# TopLevel.net
KiCad netlist of a schematic drawn in Altium Designer
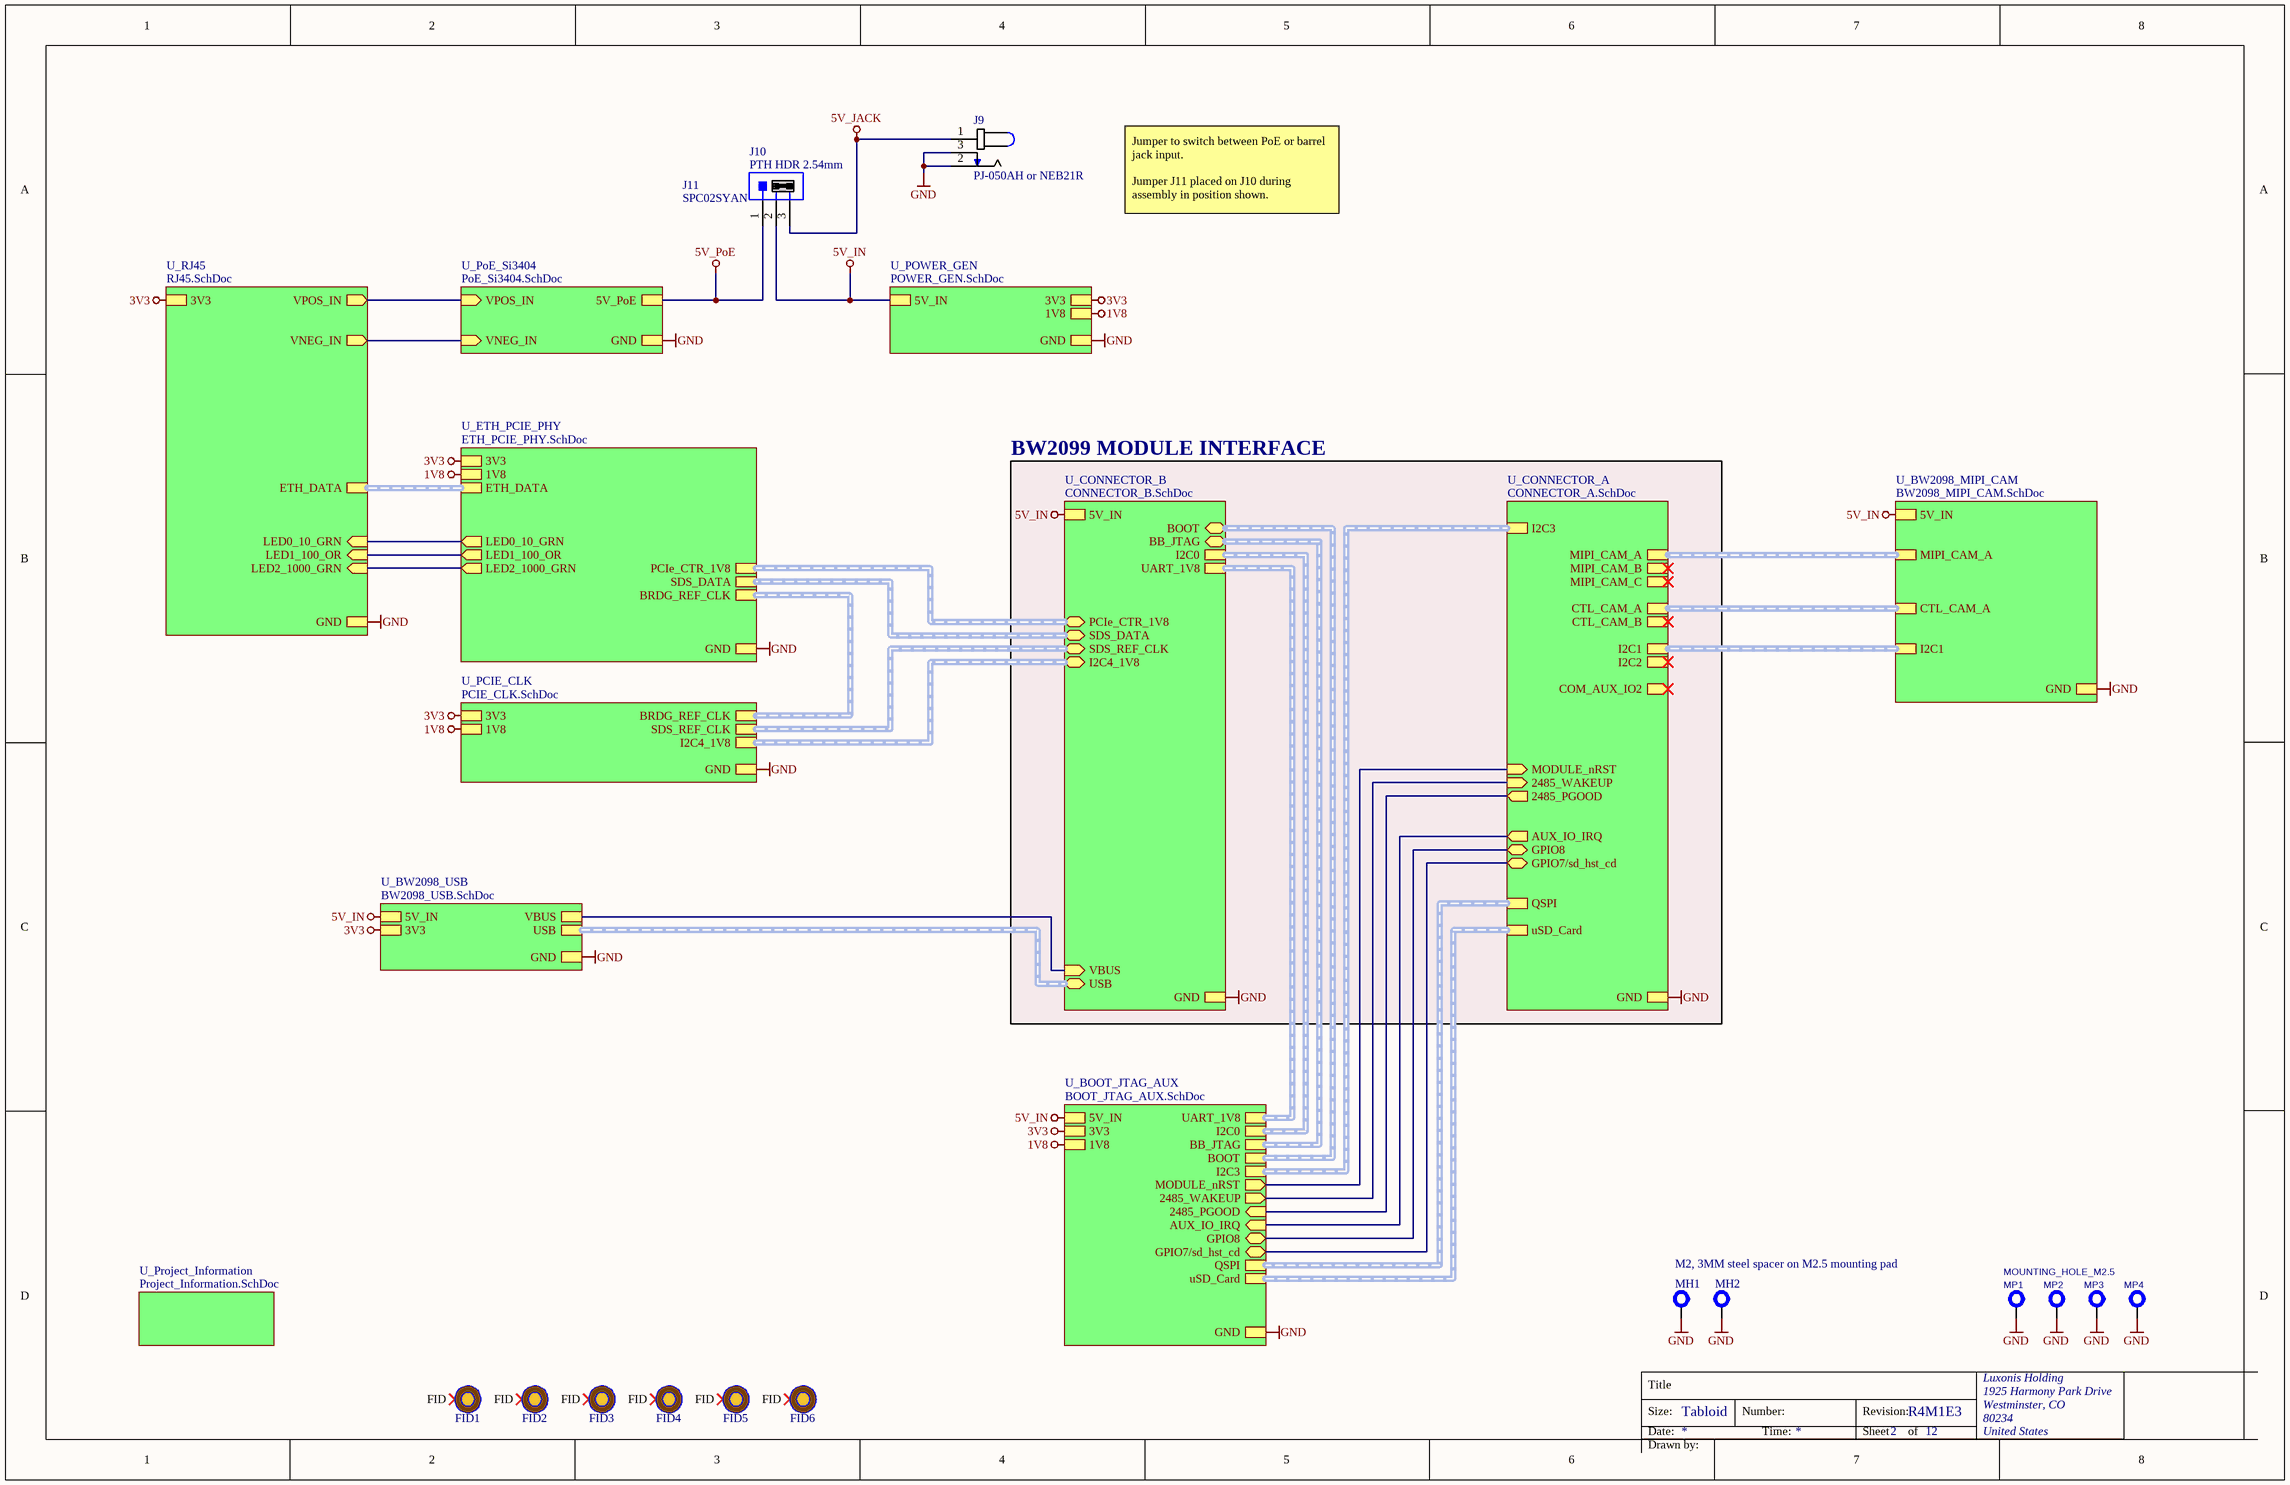
[diagram p0: TopLevel.SchDoc]

(export (version "E")
  (design (tool "Eeschema 10.0.6"))
  (components
    (comp (ref "FID1")
      (value "FIDUCIAL_ROUND_1MM")
      (footprint "LuxonisMaster:FIDUCIAL_ROUND_1MM")
      (description "Fiducial with various available footprints")
      (libsource (lib "LuxonisMaster") (part "FIDUCIAL"))
    )
    (comp (ref "FID2")
      (value "FIDUCIAL_ROUND_1MM")
      (footprint "LuxonisMaster:FIDUCIAL_ROUND_1MM")
      (description "Fiducial with various available footprints")
      (libsource (lib "LuxonisMaster") (part "FIDUCIAL"))
    )
    (comp (ref "FID3")
      (value "FIDUCIAL_ROUND_1MM")
      (footprint "LuxonisMaster:FIDUCIAL_ROUND_1MM")
      (description "Fiducial with various available footprints")
      (libsource (lib "LuxonisMaster") (part "FIDUCIAL"))
    )
    (comp (ref "FID4")
      (value "FIDUCIAL_ROUND_1MM")
      (footprint "LuxonisMaster:FIDUCIAL_ROUND_1MM")
      (description "Fiducial with various available footprints")
      (libsource (lib "LuxonisMaster") (part "FIDUCIAL"))
    )
    (comp (ref "FID5")
      (value "FIDUCIAL_ROUND_1MM")
      (footprint "LuxonisMaster:FIDUCIAL_ROUND_1MM")
      (description "Fiducial with various available footprints")
      (libsource (lib "LuxonisMaster") (part "FIDUCIAL"))
    )
    (comp (ref "FID6")
      (value "FIDUCIAL_ROUND_1MM")
      (footprint "LuxonisMaster:FIDUCIAL_ROUND_1MM")
      (description "Fiducial with various available footprints")
      (libsource (lib "LuxonisMaster") (part "FIDUCIAL"))
    )
    (comp (ref "J9")
      (value "PJ-050AH or NEB21R")
      (footprint "LuxonisMaster:PJ-050AH/NEB21R_COMBO")
      (description "CONN POWER PIN 2 POS RA PTH Barrel jack 2.1mm x 5.5mm combo footprint")
      (libsource (lib "LuxonisMaster") (part "PJ-050AH/NEB21R_COMBO"))
    )
    (comp (ref "J10")
      (value "PTH HDR 2.54mm")
      (footprint "BW2098POE:68000-103HLF")
      (description "Conn Unshrouded Header HDR 3 POS 2.54mm Solder ST Thru-Hole Bulk")
      (libsource (lib "BW2098POE") (part "68000-103HLF"))
    )
    (comp (ref "J11")
      (value "SPC02SYAN")
      (footprint "BW2098POE:SPC02SYAN")
      (description "CONN JUMPER SHORTING GOLD FLASH")
      (libsource (lib "BW2098POE") (part "SPC02SYAN"))
    )
    (comp (ref "MH1")
      (value "M2, 3MM steel spacer on M2.5 mounting pad")
      (footprint "LuxonisMaster:9774030243R")
      (description "MP ROUND STANDOFF M2X0.4 STEEL 3MM")
      (libsource (lib "LuxonisMaster") (part "9774030243R"))
    )
    (comp (ref "MH2")
      (value "M2, 3MM steel spacer on M2.5 mounting pad")
      (footprint "LuxonisMaster:9774030243R")
      (description "MP ROUND STANDOFF M2X0.4 STEEL 3MM")
      (libsource (lib "LuxonisMaster") (part "9774030243R"))
    )
    (comp (ref "MP1")
      (value "MOUNTING_HOLE_M2.5")
      (footprint "LuxonisMaster:MOUNTING_HOLE_M2.5")
      (description "=CurrentFootprint")
      (libsource (lib "LuxonisMaster") (part "MP_Mounting-Holes"))
    )
    (comp (ref "MP2")
      (value "MOUNTING_HOLE_M2.5")
      (footprint "LuxonisMaster:MOUNTING_HOLE_M2.5")
      (description "=CurrentFootprint")
      (libsource (lib "LuxonisMaster") (part "MP_Mounting-Holes"))
    )
    (comp (ref "MP3")
      (value "MOUNTING_HOLE_M2.5")
      (footprint "LuxonisMaster:MOUNTING_HOLE_M2.5")
      (description "=CurrentFootprint")
      (libsource (lib "LuxonisMaster") (part "MP_Mounting-Holes"))
    )
    (comp (ref "MP4")
      (value "MOUNTING_HOLE_M2.5")
      (footprint "LuxonisMaster:MOUNTING_HOLE_M2.5")
      (description "=CurrentFootprint")
      (libsource (lib "LuxonisMaster") (part "MP_Mounting-Holes"))
    )
  )
  (nets
    (net (code "37") (name "5V_IN") (class "Default")
      (node (ref "J10") (pin "2") (pinfunction "2_2") (pintype "passive"))
    )
    (net (code "38") (name "5V_JACK") (class "Default")
      (node (ref "J10") (pin "3") (pinfunction "3_3") (pintype "passive"))
      (node (ref "J9") (pin "1") (pinfunction "1_1") (pintype "passive"))
    )
    (net (code "39") (name "5V_PoE") (class "Default")
      (node (ref "J10") (pin "1") (pinfunction "1_1") (pintype "passive"))
    )
    (net (code "40") (name "GND") (class "Default")
      (node (ref "J9") (pin "2") (pinfunction "2_2") (pintype "passive"))
      (node (ref "J9") (pin "3") (pinfunction "3_3") (pintype "passive"))
      (node (ref "MH1") (pin "1") (pintype "passive"))
      (node (ref "MH2") (pin "1") (pintype "passive"))
      (node (ref "MP1") (pin "1") (pintype "passive"))
      (node (ref "MP2") (pin "1") (pintype "passive"))
      (node (ref "MP3") (pin "1") (pintype "passive"))
      (node (ref "MP4") (pin "1") (pintype "passive"))
    )
    (net (code "41") (name "unconnected-(FID1-PadFID)") (class "Default")
      (node (ref "FID1") (pin "FID") (pinfunction "FID_FID") (pintype "input+no_connect"))
    )
    (net (code "42") (name "unconnected-(FID2-PadFID)") (class "Default")
      (node (ref "FID2") (pin "FID") (pinfunction "FID_FID") (pintype "input+no_connect"))
    )
    (net (code "43") (name "unconnected-(FID3-PadFID)") (class "Default")
      (node (ref "FID3") (pin "FID") (pinfunction "FID_FID") (pintype "input+no_connect"))
    )
    (net (code "44") (name "unconnected-(FID4-PadFID)") (class "Default")
      (node (ref "FID4") (pin "FID") (pinfunction "FID_FID") (pintype "input+no_connect"))
    )
    (net (code "45") (name "unconnected-(FID5-PadFID)") (class "Default")
      (node (ref "FID5") (pin "FID") (pinfunction "FID_FID") (pintype "input+no_connect"))
    )
    (net (code "46") (name "unconnected-(FID6-PadFID)") (class "Default")
      (node (ref "FID6") (pin "FID") (pinfunction "FID_FID") (pintype "input+no_connect"))
    )
  )
)
